# IO_EXPANDER.net
KiCad netlist of a schematic drawn in Altium Designer
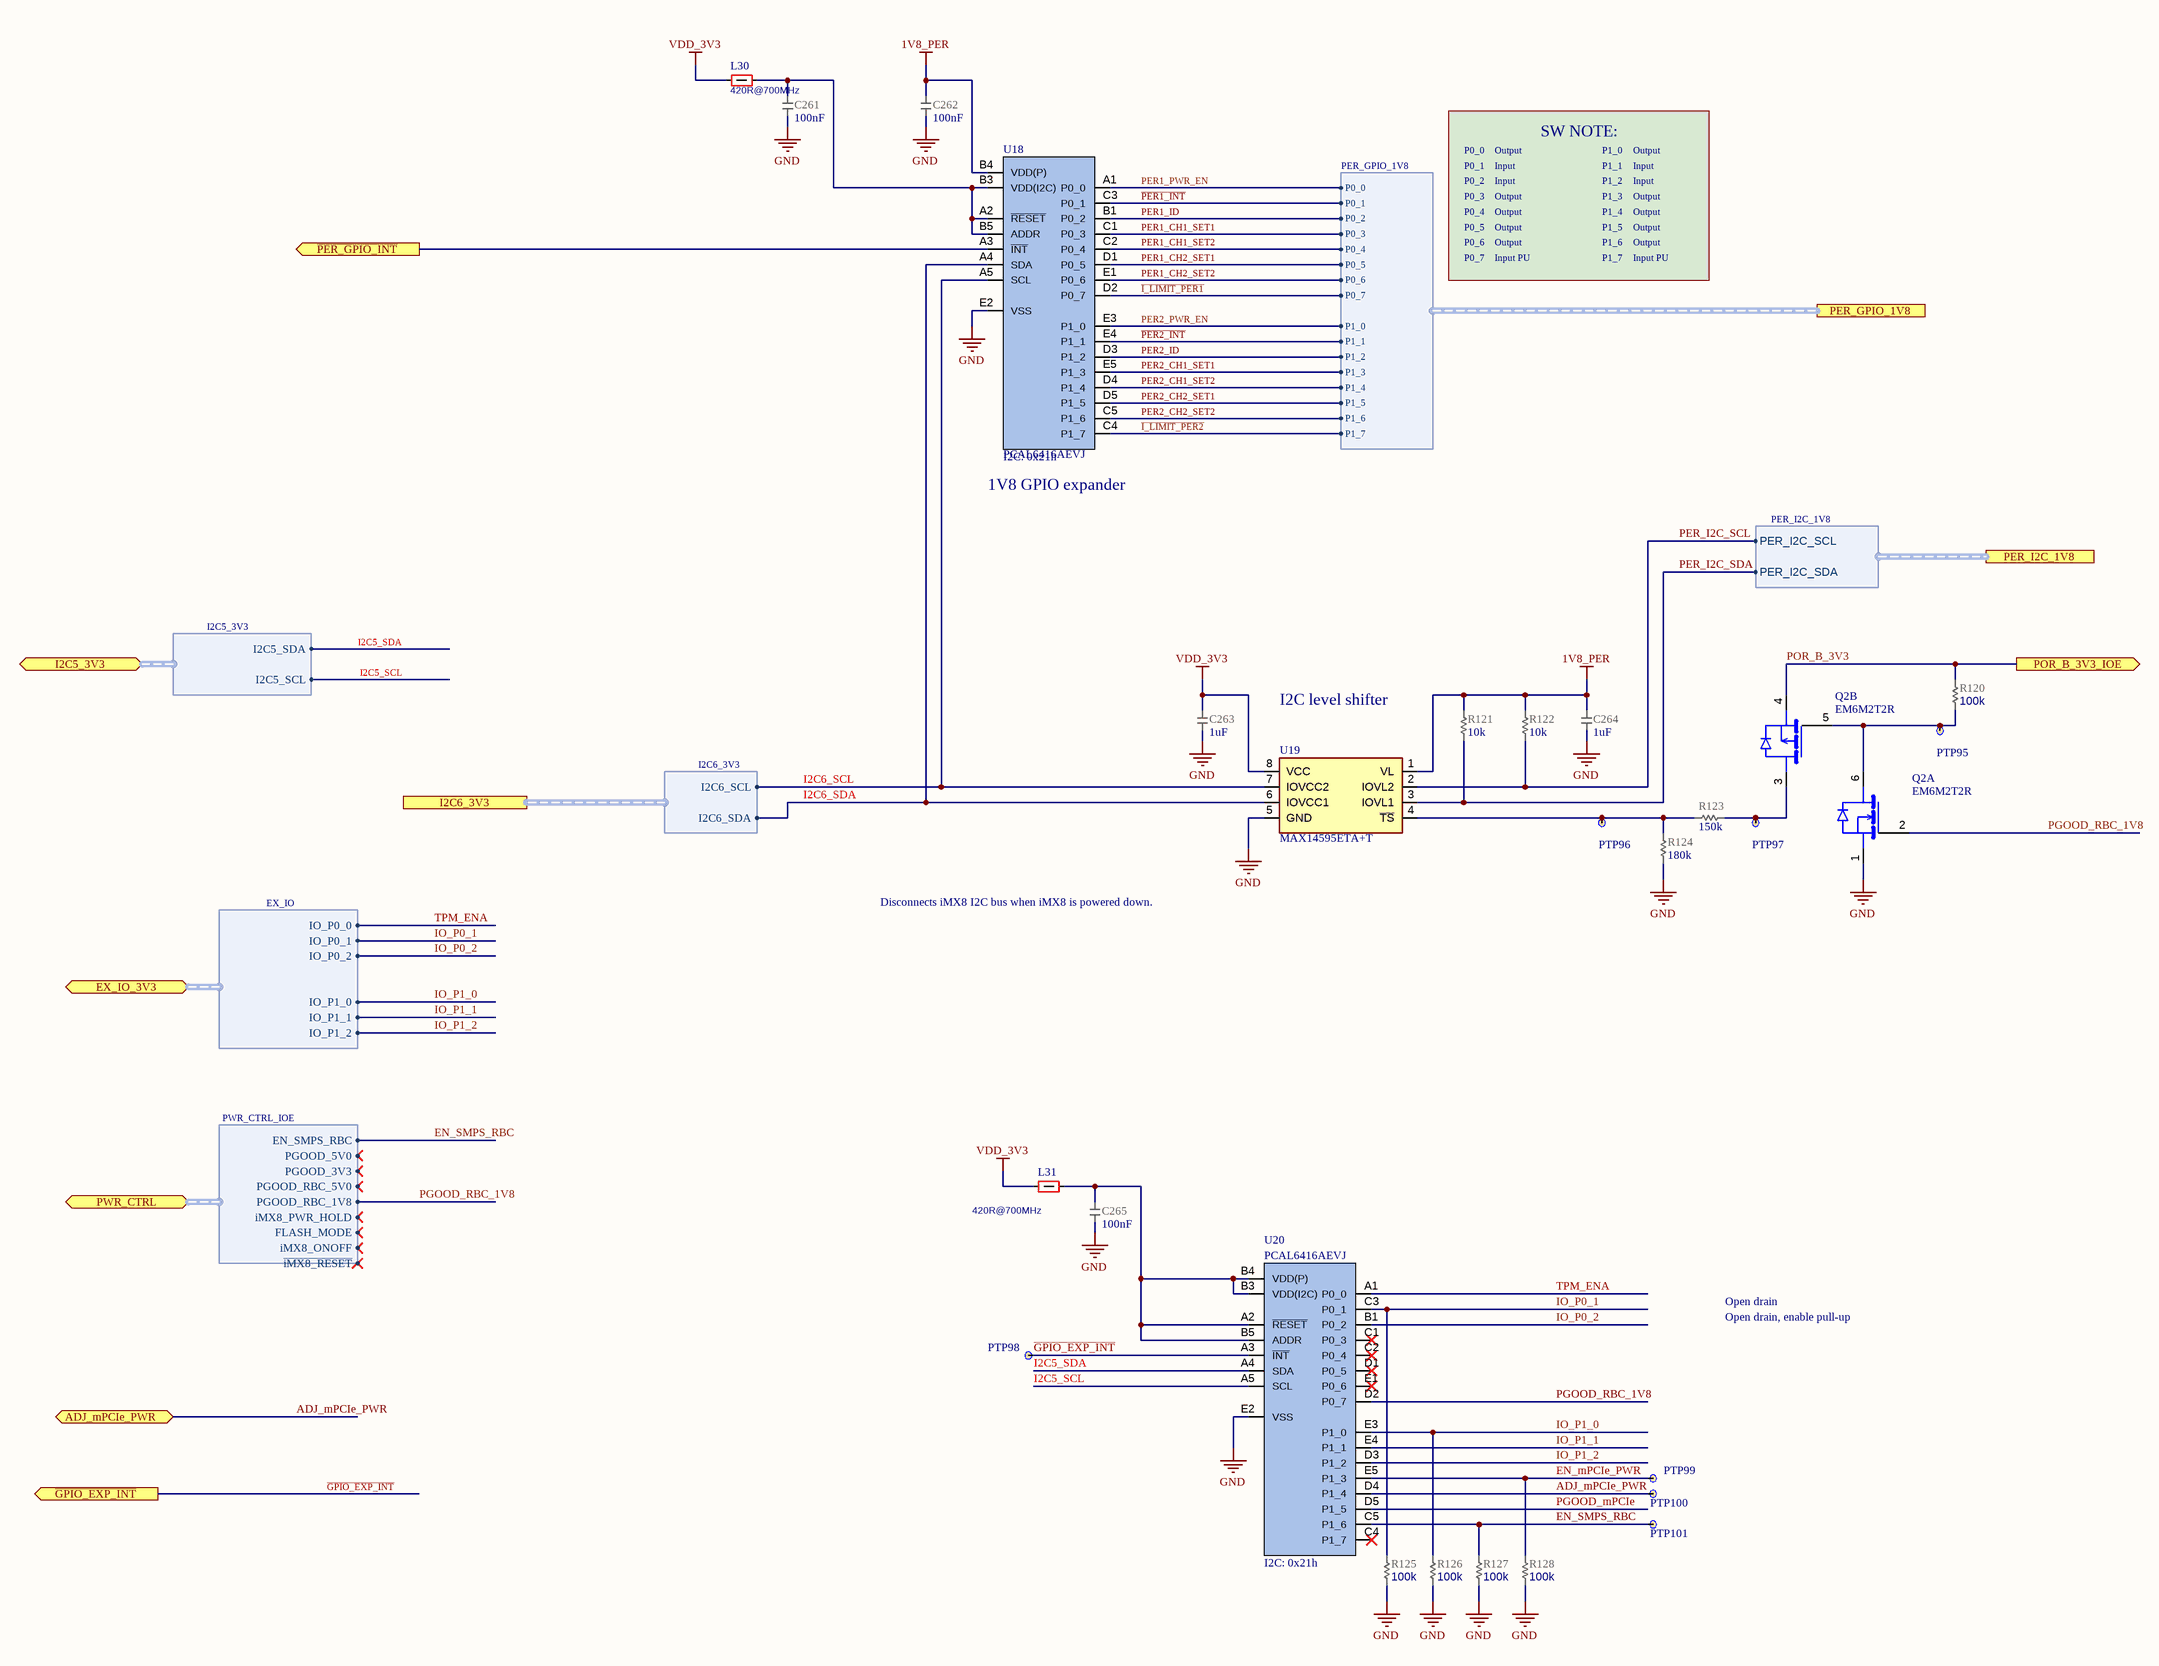
[diagram p0: IO_EXPANDER.SchDoc]

(export (version "E")
  (design (tool "Eeschema 10.0.6"))
  (components
    (comp (ref "C261")
      (value "100nF")
      (footprint "CAP_0201_UN1Q")
      (description "CAP")
      (fields (field (name "PART NUMBER") "GRM033C71C104KE14D") (field (name "MANUFACTURER") "Murata"))
      (libsource (lib "robo_cam") (part "CMP-001-000385-16"))
    )
    (comp (ref "C262")
      (value "100nF")
      (footprint "CAP_0201_UN1Q")
      (description "CAP")
      (fields (field (name "PART NUMBER") "GRM033C71C104KE14D") (field (name "MANUFACTURER") "Murata"))
      (libsource (lib "robo_cam") (part "CMP-001-000385-16"))
    )
    (comp (ref "C263")
      (value "1uF")
      (footprint "CAP_0201_UN1Q")
      (description "CAP")
      (fields (field (name "PART NUMBER") "KGM03CS61A105MH") (field (name "MANUFACTURER") "Kyocera"))
      (libsource (lib "robo_cam") (part "CMP-001-000336-15"))
    )
    (comp (ref "C264")
      (value "1uF")
      (footprint "CAP_0201_UN1Q")
      (description "CAP")
      (fields (field (name "PART NUMBER") "KGM03CS61A105MH") (field (name "MANUFACTURER") "Kyocera"))
      (libsource (lib "robo_cam") (part "CMP-001-000336-15"))
    )
    (comp (ref "C265")
      (value "100nF")
      (footprint "CAP_0201_UN1Q")
      (description "CAP")
      (fields (field (name "PART NUMBER") "GRM033C71C104KE14D") (field (name "MANUFACTURER") "Murata"))
      (libsource (lib "robo_cam") (part "CMP-001-000385-16"))
    )
    (comp (ref "L30")
      (value "420R@700MHz")
      (footprint "IND_0201_UN1Q")
      (description "FERRITE")
      (fields (field (name "TOLERANCE") "25%") (field (name "PART NUMBER") "BLF03JD421GZE"))
      (libsource (lib "robo_cam") (part "CMP-001-000747-7"))
    )
    (comp (ref "L31")
      (value "420R@700MHz")
      (footprint "IND_0201_UN1Q")
      (description "FERRITE")
      (fields (field (name "TOLERANCE") "25%") (field (name "PART NUMBER") "BLF03JD421GZE"))
      (libsource (lib "robo_cam") (part "CMP-001-000747-7"))
    )
    (comp (ref "PTP95")
      (value "PTP_0.4mm")
      (footprint "PTP_0.4mm")
      (description "Production Testpoint 0.4mm. Flying probe. Use 1mm pitch.")
      (fields (field (name "PART NUMBER") "PTP 0.4mm"))
      (libsource (lib "robo_cam") (part "CMP-001-001296-3"))
    )
    (comp (ref "PTP96")
      (value "PTP_0.4mm")
      (footprint "PTP_0.4mm")
      (description "Production Testpoint 0.4mm. Flying probe. Use 1mm pitch.")
      (fields (field (name "PART NUMBER") "PTP 0.4mm"))
      (libsource (lib "robo_cam") (part "CMP-001-001296-3"))
    )
    (comp (ref "PTP97")
      (value "PTP_0.4mm")
      (footprint "PTP_0.4mm")
      (description "Production Testpoint 0.4mm. Flying probe. Use 1mm pitch.")
      (fields (field (name "PART NUMBER") "PTP 0.4mm"))
      (libsource (lib "robo_cam") (part "CMP-001-001296-3"))
    )
    (comp (ref "PTP98")
      (value "PTP_0.4mm")
      (footprint "PTP_0.4mm")
      (description "Production Testpoint 0.4mm. Flying probe. Use 1mm pitch.")
      (fields (field (name "PART NUMBER") "PTP 0.4mm"))
      (libsource (lib "robo_cam") (part "CMP-001-001296-3"))
    )
    (comp (ref "PTP99")
      (value "PTP_0.4mm")
      (footprint "PTP_0.4mm")
      (description "Production Testpoint 0.4mm. Flying probe. Use 1mm pitch.")
      (fields (field (name "PART NUMBER") "PTP 0.4mm"))
      (libsource (lib "robo_cam") (part "CMP-001-001296-3"))
    )
    (comp (ref "PTP100")
      (value "PTP_0.4mm")
      (footprint "PTP_0.4mm")
      (description "Production Testpoint 0.4mm. Flying probe. Use 1mm pitch.")
      (fields (field (name "PART NUMBER") "PTP 0.4mm"))
      (libsource (lib "robo_cam") (part "CMP-001-001296-3"))
    )
    (comp (ref "PTP101")
      (value "PTP_0.4mm")
      (footprint "PTP_0.4mm")
      (description "Production Testpoint 0.4mm. Flying probe. Use 1mm pitch.")
      (fields (field (name "PART NUMBER") "PTP 0.4mm"))
      (libsource (lib "robo_cam") (part "CMP-001-001296-3"))
    )
    (comp (ref "Q2")
      (value "EM6M2T2R")
      (footprint "SOT-563")
      (description "Dual Nch + Pch MOSFET 20V 200mA")
      (fields
        (field (name "MANUFACTURER") "ROHM")
        (field (name "PART NUMBER") "EM6M2T2R")
        (field (name "SOURCE") "UUDET_KOMPONENTIT.SchLib")
      )
      (libsource (lib "robo_cam") (part "CMP-031-000021-4"))
    )
    (comp (ref "R120")
      (value "100k")
      (footprint "RES_0201_UN1Q")
      (description "RES")
      (fields (field (name "TOLERANCE") "1%") (field (name "PART NUMBER") "RC0201FR-07100KL"))
      (libsource (lib "robo_cam") (part "CMP-001-000526-11"))
    )
    (comp (ref "R121")
      (value "10k")
      (footprint "RES_0201_UN1Q")
      (description "RES")
      (fields (field (name "PART NUMBER") "RC0201FR-0710KL") (field (name "MANUFACTURER") "YAGEO"))
      (libsource (lib "robo_cam") (part "CMP-001-000446-13"))
    )
    (comp (ref "R122")
      (value "10k")
      (footprint "RES_0201_UN1Q")
      (description "RES")
      (fields (field (name "PART NUMBER") "RC0201FR-0710KL") (field (name "MANUFACTURER") "YAGEO"))
      (libsource (lib "robo_cam") (part "CMP-001-000446-13"))
    )
    (comp (ref "R123")
      (value "150k")
      (footprint "RES_0201_UN1Q")
      (description "RES")
      (fields (field (name "PART NUMBER") "RC0201FR-07150KL") (field (name "MANUFACTURER") "YAGEO"))
      (libsource (lib "robo_cam") (part "CMP-001-000538-13"))
    )
    (comp (ref "R124")
      (value "180k")
      (footprint "RES_0201_UN1Q")
      (description "RES")
      (fields (field (name "PART NUMBER") "RC0201FR-07180KL") (field (name "MANUFACTURER") "YAGEO"))
      (libsource (lib "robo_cam") (part "CMP-001-000543-12"))
    )
    (comp (ref "R125")
      (value "100k")
      (footprint "RES_0201_UN1Q")
      (description "RES")
      (fields (field (name "TOLERANCE") "1%") (field (name "PART NUMBER") "RC0201FR-07100KL"))
      (libsource (lib "robo_cam") (part "CMP-001-000526-11"))
    )
    (comp (ref "R126")
      (value "100k")
      (footprint "RES_0201_UN1Q")
      (description "RES")
      (fields (field (name "TOLERANCE") "1%") (field (name "PART NUMBER") "RC0201FR-07100KL"))
      (libsource (lib "robo_cam") (part "CMP-001-000526-11"))
    )
    (comp (ref "R127")
      (value "100k")
      (footprint "RES_0201_UN1Q")
      (description "RES")
      (fields (field (name "TOLERANCE") "1%") (field (name "PART NUMBER") "RC0201FR-07100KL"))
      (libsource (lib "robo_cam") (part "CMP-001-000526-11"))
    )
    (comp (ref "R128")
      (value "100k")
      (footprint "RES_0201_UN1Q")
      (description "RES")
      (fields (field (name "TOLERANCE") "1%") (field (name "PART NUMBER") "RC0201FR-07100KL"))
      (libsource (lib "robo_cam") (part "CMP-001-000526-11"))
    )
    (comp (ref "U18")
      (value "PCAL6416AEVJ_VFBGA24")
      (footprint "VFBGA24P50_300X300X100_NXP")
      (description "I/O Expander 16-Bit I²C, SMBus, 0.5mm pitch")
      (fields
        (field (name "MANUFACTURER") "NXP")
        (field (name "PART NUMBER") "PCAL6416AEVJ")
        (field (name "MANUFACTURER_1") "NXP Semiconductors")
        (field (name "SOURCE") "UUDET_KOMPONENTIT.SchLib")
      )
      (libsource (lib "robo_cam") (part "CMP-031-000208-3"))
    )
    (comp (ref "U19")
      (value "MAX14595ETA+T")
      (footprint "MAX14591_SON50P200X200X80-8N")
      (description "High speed, Open-Drain capable logic level translator. Pin compatible with MAX14591ETA.")
      (fields
        (field (name "MANUFACTURER") "Maxim Integrated")
        (field (name "PART NUMBER") "MAX14595ETA+T")
        (field (name "MANUFACTURER_1") "Maxim")
        (field (name "SOURCE") "UUDET_KOMPONENTIT.SchLib")
      )
      (libsource (lib "robo_cam") (part "CMP-031-000171-3"))
    )
    (comp (ref "U20")
      (value "PCAL6416AEVJ_VFBGA24")
      (footprint "VFBGA24P50_300X300X100_NXP")
      (description "I/O Expander 16-Bit I²C, SMBus, 0.5mm pitch")
      (fields
        (field (name "MANUFACTURER") "NXP")
        (field (name "PART NUMBER") "PCAL6416AEVJ")
        (field (name "SOURCE") "UUDET_KOMPONENTIT.SchLib")
      )
      (libsource (lib "TII_WS") (part "PCAL6416AEVJ_VFBGA24"))
    )
  )
  (nets
    (net (code "7") (name "/ADJ_mPCIe_PWR") (class "Default")
      (node (ref "PTP100") (pin "1") (pinfunction "TP_1") (pintype "passive"))
      (node (ref "U20") (pin "D4") (pinfunction "P1_4_D4") (pintype "passive"))
    )
    (net (code "8") (name "/EN_SMPS_RBC") (class "Default")
      (node (ref "PTP101") (pin "1") (pinfunction "TP_1") (pintype "passive"))
      (node (ref "R127") (pin "2") (pinfunction "2_2") (pintype "passive"))
      (node (ref "U20") (pin "C5") (pinfunction "P1_6_C5") (pintype "passive"))
    )
    (net (code "9") (name "/EN_mPCIe_PWR") (class "Default")
      (node (ref "PTP99") (pin "1") (pinfunction "TP_1") (pintype "passive"))
      (node (ref "R128") (pin "2") (pinfunction "2_2") (pintype "passive"))
      (node (ref "U20") (pin "E5") (pinfunction "P1_3_E5") (pintype "passive"))
    )
    (net (code "10") (name "/GPIO_EXP_INT") (class "Default")
      (node (ref "PTP98") (pin "1") (pinfunction "TP_1") (pintype "passive"))
      (node (ref "U20") (pin "A3") (pinfunction "INT_A3") (pintype "passive"))
    )
    (net (code "11") (name "/I2C5_SCL") (class "Default")
      (node (ref "U20") (pin "A5") (pinfunction "SCL_A5") (pintype "passive"))
    )
    (net (code "12") (name "/I2C5_SDA") (class "Default")
      (node (ref "U20") (pin "A4") (pinfunction "SDA_A4") (pintype "passive"))
    )
    (net (code "13") (name "/I2C6_SCL") (class "Default")
      (node (ref "U18") (pin "A5") (pinfunction "SCL_A5") (pintype "passive"))
      (node (ref "U19") (pin "7") (pinfunction "IOVCC2_7") (pintype "passive"))
    )
    (net (code "14") (name "/I2C6_SDA") (class "Default")
      (node (ref "U18") (pin "A4") (pinfunction "SDA_A4") (pintype "passive"))
      (node (ref "U19") (pin "6") (pinfunction "IOVCC1_6") (pintype "passive"))
    )
    (net (code "15") (name "/IO_P0_1") (class "Default")
      (node (ref "R125") (pin "2") (pinfunction "2_2") (pintype "passive"))
      (node (ref "U20") (pin "C3") (pinfunction "P0_1_C3") (pintype "passive"))
    )
    (net (code "16") (name "/IO_P0_2") (class "Default")
      (node (ref "U20") (pin "B1") (pinfunction "P0_2_B1") (pintype "passive"))
    )
    (net (code "17") (name "/IO_P1_0") (class "Default")
      (node (ref "R126") (pin "2") (pinfunction "2_2") (pintype "passive"))
      (node (ref "U20") (pin "E3") (pinfunction "P1_0_E3") (pintype "passive"))
    )
    (net (code "18") (name "/IO_P1_1") (class "Default")
      (node (ref "U20") (pin "E4") (pinfunction "P1_1_E4") (pintype "passive"))
    )
    (net (code "19") (name "/IO_P1_2") (class "Default")
      (node (ref "U20") (pin "D3") (pinfunction "P1_2_D3") (pintype "passive"))
    )
    (net (code "20") (name "/I_LIMIT_PER1") (class "Default")
      (node (ref "U18") (pin "D2") (pinfunction "P0_7_D2") (pintype "passive"))
    )
    (net (code "21") (name "/I_LIMIT_PER2") (class "Default")
      (node (ref "U18") (pin "C4") (pinfunction "P1_7_C4") (pintype "passive"))
    )
    (net (code "22") (name "/PER1_CH1_SET1") (class "Default")
      (node (ref "U18") (pin "C1") (pinfunction "P0_3_C1") (pintype "passive"))
    )
    (net (code "23") (name "/PER1_CH1_SET2") (class "Default")
      (node (ref "U18") (pin "C2") (pinfunction "P0_4_C2") (pintype "passive"))
    )
    (net (code "24") (name "/PER1_CH2_SET1") (class "Default")
      (node (ref "U18") (pin "D1") (pinfunction "P0_5_D1") (pintype "passive"))
    )
    (net (code "25") (name "/PER1_CH2_SET2") (class "Default")
      (node (ref "U18") (pin "E1") (pinfunction "P0_6_E1") (pintype "passive"))
    )
    (net (code "26") (name "/PER1_ID") (class "Default")
      (node (ref "U18") (pin "B1") (pinfunction "P0_2_B1") (pintype "passive"))
    )
    (net (code "27") (name "/PER1_INT") (class "Default")
      (node (ref "U18") (pin "C3") (pinfunction "P0_1_C3") (pintype "passive"))
    )
    (net (code "28") (name "/PER1_PWR_EN") (class "Default")
      (node (ref "U18") (pin "A1") (pinfunction "P0_0_A1") (pintype "passive"))
    )
    (net (code "29") (name "/PER2_CH1_SET1") (class "Default")
      (node (ref "U18") (pin "E5") (pinfunction "P1_3_E5") (pintype "passive"))
    )
    (net (code "30") (name "/PER2_CH1_SET2") (class "Default")
      (node (ref "U18") (pin "D4") (pinfunction "P1_4_D4") (pintype "passive"))
    )
    (net (code "31") (name "/PER2_CH2_SET1") (class "Default")
      (node (ref "U18") (pin "D5") (pinfunction "P1_5_D5") (pintype "passive"))
    )
    (net (code "32") (name "/PER2_CH2_SET2") (class "Default")
      (node (ref "U18") (pin "C5") (pinfunction "P1_6_C5") (pintype "passive"))
    )
    (net (code "33") (name "/PER2_ID") (class "Default")
      (node (ref "U18") (pin "D3") (pinfunction "P1_2_D3") (pintype "passive"))
    )
    (net (code "34") (name "/PER2_INT") (class "Default")
      (node (ref "U18") (pin "E4") (pinfunction "P1_1_E4") (pintype "passive"))
    )
    (net (code "35") (name "/PER2_PWR_EN") (class "Default")
      (node (ref "U18") (pin "E3") (pinfunction "P1_0_E3") (pintype "passive"))
    )
    (net (code "36") (name "/PER_GPIO_INT") (class "Default")
      (node (ref "U18") (pin "A3") (pinfunction "INT_A3") (pintype "passive"))
    )
    (net (code "37") (name "/PER_I2C_SCL") (class "Default")
      (node (ref "R122") (pin "1") (pinfunction "1_1") (pintype "passive"))
      (node (ref "U19") (pin "2") (pinfunction "IOVL2_2") (pintype "passive"))
    )
    (net (code "38") (name "/PER_I2C_SDA") (class "Default")
      (node (ref "R121") (pin "1") (pinfunction "1_1") (pintype "passive"))
      (node (ref "U19") (pin "3") (pinfunction "IOVL1_3") (pintype "passive"))
    )
    (net (code "39") (name "/PGOOD_RBC_1V8") (class "Default")
      (node (ref "Q2") (pin "2") (pinfunction "G_2") (pintype "passive"))
      (node (ref "U20") (pin "D2") (pinfunction "P0_7_D2") (pintype "passive"))
    )
    (net (code "40") (name "/PGOOD_mPCIe") (class "Default")
      (node (ref "U20") (pin "D5") (pinfunction "P1_5_D5") (pintype "passive"))
    )
    (net (code "41") (name "/POR_B_3V3") (class "Default")
      (node (ref "Q2") (pin "4") (pinfunction "S_4") (pintype "passive"))
      (node (ref "R120") (pin "2") (pinfunction "2_2") (pintype "passive"))
    )
    (net (code "42") (name "/TPM_ENA") (class "Default")
      (node (ref "U20") (pin "A1") (pinfunction "P0_0_A1") (pintype "passive"))
    )
    (net (code "49") (name "1V8_PER") (class "Default")
      (node (ref "C262") (pin "2") (pinfunction "2_2") (pintype "passive"))
      (node (ref "C264") (pin "2") (pinfunction "2_2") (pintype "passive"))
      (node (ref "R121") (pin "2") (pinfunction "2_2") (pintype "passive"))
      (node (ref "R122") (pin "2") (pinfunction "2_2") (pintype "passive"))
      (node (ref "U18") (pin "B4") (pinfunction "VDD(P)_B4") (pintype "power_in"))
      (node (ref "U19") (pin "1") (pinfunction "VL_1") (pintype "passive"))
    )
    (net (code "50") (name "GND") (class "Default")
      (node (ref "C261") (pin "1") (pinfunction "1_1") (pintype "passive"))
      (node (ref "C262") (pin "1") (pinfunction "1_1") (pintype "passive"))
      (node (ref "C263") (pin "1") (pinfunction "1_1") (pintype "passive"))
      (node (ref "C264") (pin "1") (pinfunction "1_1") (pintype "passive"))
      (node (ref "C265") (pin "1") (pinfunction "1_1") (pintype "passive"))
      (node (ref "Q2") (pin "1") (pinfunction "S_1") (pintype "passive"))
      (node (ref "R124") (pin "1") (pinfunction "1_1") (pintype "passive"))
      (node (ref "R125") (pin "1") (pinfunction "1_1") (pintype "passive"))
      (node (ref "R126") (pin "1") (pinfunction "1_1") (pintype "passive"))
      (node (ref "R127") (pin "1") (pinfunction "1_1") (pintype "passive"))
      (node (ref "R128") (pin "1") (pinfunction "1_1") (pintype "passive"))
      (node (ref "U18") (pin "E2") (pinfunction "VSS_E2") (pintype "power_in"))
      (node (ref "U19") (pin "5") (pinfunction "GND_5") (pintype "passive"))
      (node (ref "U20") (pin "E2") (pinfunction "VSS_E2") (pintype "power_in"))
    )
    (net (code "51") (name "Net-(PTP95-TP)") (class "Default")
      (node (ref "PTP95") (pin "1") (pinfunction "TP_1") (pintype "passive"))
      (node (ref "Q2") (pin "5") (pinfunction "G_5") (pintype "passive"))
      (node (ref "Q2") (pin "6") (pinfunction "D_6") (pintype "passive"))
      (node (ref "R120") (pin "1") (pinfunction "1_1") (pintype "passive"))
    )
    (net (code "52") (name "Net-(PTP96-TP)") (class "Default")
      (node (ref "PTP96") (pin "1") (pinfunction "TP_1") (pintype "passive"))
      (node (ref "R123") (pin "1") (pinfunction "1_1") (pintype "passive"))
      (node (ref "R124") (pin "2") (pinfunction "2_2") (pintype "passive"))
      (node (ref "U19") (pin "4") (pinfunction "~{TS}_4") (pintype "passive"))
    )
    (net (code "53") (name "Net-(PTP97-TP)") (class "Default")
      (node (ref "PTP97") (pin "1") (pinfunction "TP_1") (pintype "passive"))
      (node (ref "Q2") (pin "3") (pinfunction "D_3") (pintype "passive"))
      (node (ref "R123") (pin "2") (pinfunction "2_2") (pintype "passive"))
    )
    (net (code "54") (name "Net-(U18-ADDR)") (class "Default")
      (node (ref "C261") (pin "2") (pinfunction "2_2") (pintype "passive"))
      (node (ref "L30") (pin "2") (pinfunction "2_2") (pintype "passive"))
      (node (ref "U18") (pin "A2") (pinfunction "RESET_A2") (pintype "passive"))
      (node (ref "U18") (pin "B3") (pinfunction "VDD(I2C)_B3") (pintype "power_in"))
      (node (ref "U18") (pin "B5") (pinfunction "ADDR_B5") (pintype "passive"))
    )
    (net (code "55") (name "Net-(U20-ADDR)") (class "Default")
      (node (ref "C265") (pin "2") (pinfunction "2_2") (pintype "passive"))
      (node (ref "L31") (pin "2") (pinfunction "2_2") (pintype "passive"))
      (node (ref "U20") (pin "A2") (pinfunction "RESET_A2") (pintype "passive"))
      (node (ref "U20") (pin "B3") (pinfunction "VDD(I2C)_B3") (pintype "power_in"))
      (node (ref "U20") (pin "B4") (pinfunction "VDD(P)_B4") (pintype "power_in"))
      (node (ref "U20") (pin "B5") (pinfunction "ADDR_B5") (pintype "passive"))
    )
    (net (code "56") (name "VDD_3V3") (class "Default")
      (node (ref "C263") (pin "2") (pinfunction "2_2") (pintype "passive"))
      (node (ref "L30") (pin "1") (pinfunction "1_1") (pintype "passive"))
      (node (ref "L31") (pin "1") (pinfunction "1_1") (pintype "passive"))
      (node (ref "U19") (pin "8") (pinfunction "VCC_8") (pintype "passive"))
    )
    (net (code "57") (name "unconnected-(U20-P0_3-PadC1)") (class "Default")
      (node (ref "U20") (pin "C1") (pinfunction "P0_3_C1") (pintype "passive+no_connect"))
    )
    (net (code "58") (name "unconnected-(U20-P0_4-PadC2)") (class "Default")
      (node (ref "U20") (pin "C2") (pinfunction "P0_4_C2") (pintype "passive+no_connect"))
    )
    (net (code "59") (name "unconnected-(U20-P0_5-PadD1)") (class "Default")
      (node (ref "U20") (pin "D1") (pinfunction "P0_5_D1") (pintype "passive+no_connect"))
    )
    (net (code "60") (name "unconnected-(U20-P0_6-PadE1)") (class "Default")
      (node (ref "U20") (pin "E1") (pinfunction "P0_6_E1") (pintype "passive+no_connect"))
    )
    (net (code "61") (name "unconnected-(U20-P1_7-PadC4)") (class "Default")
      (node (ref "U20") (pin "C4") (pinfunction "P1_7_C4") (pintype "passive+no_connect"))
    )
  )
)
